# old_motor_line.net
KiCad netlist of a schematic drawn in EAGLE
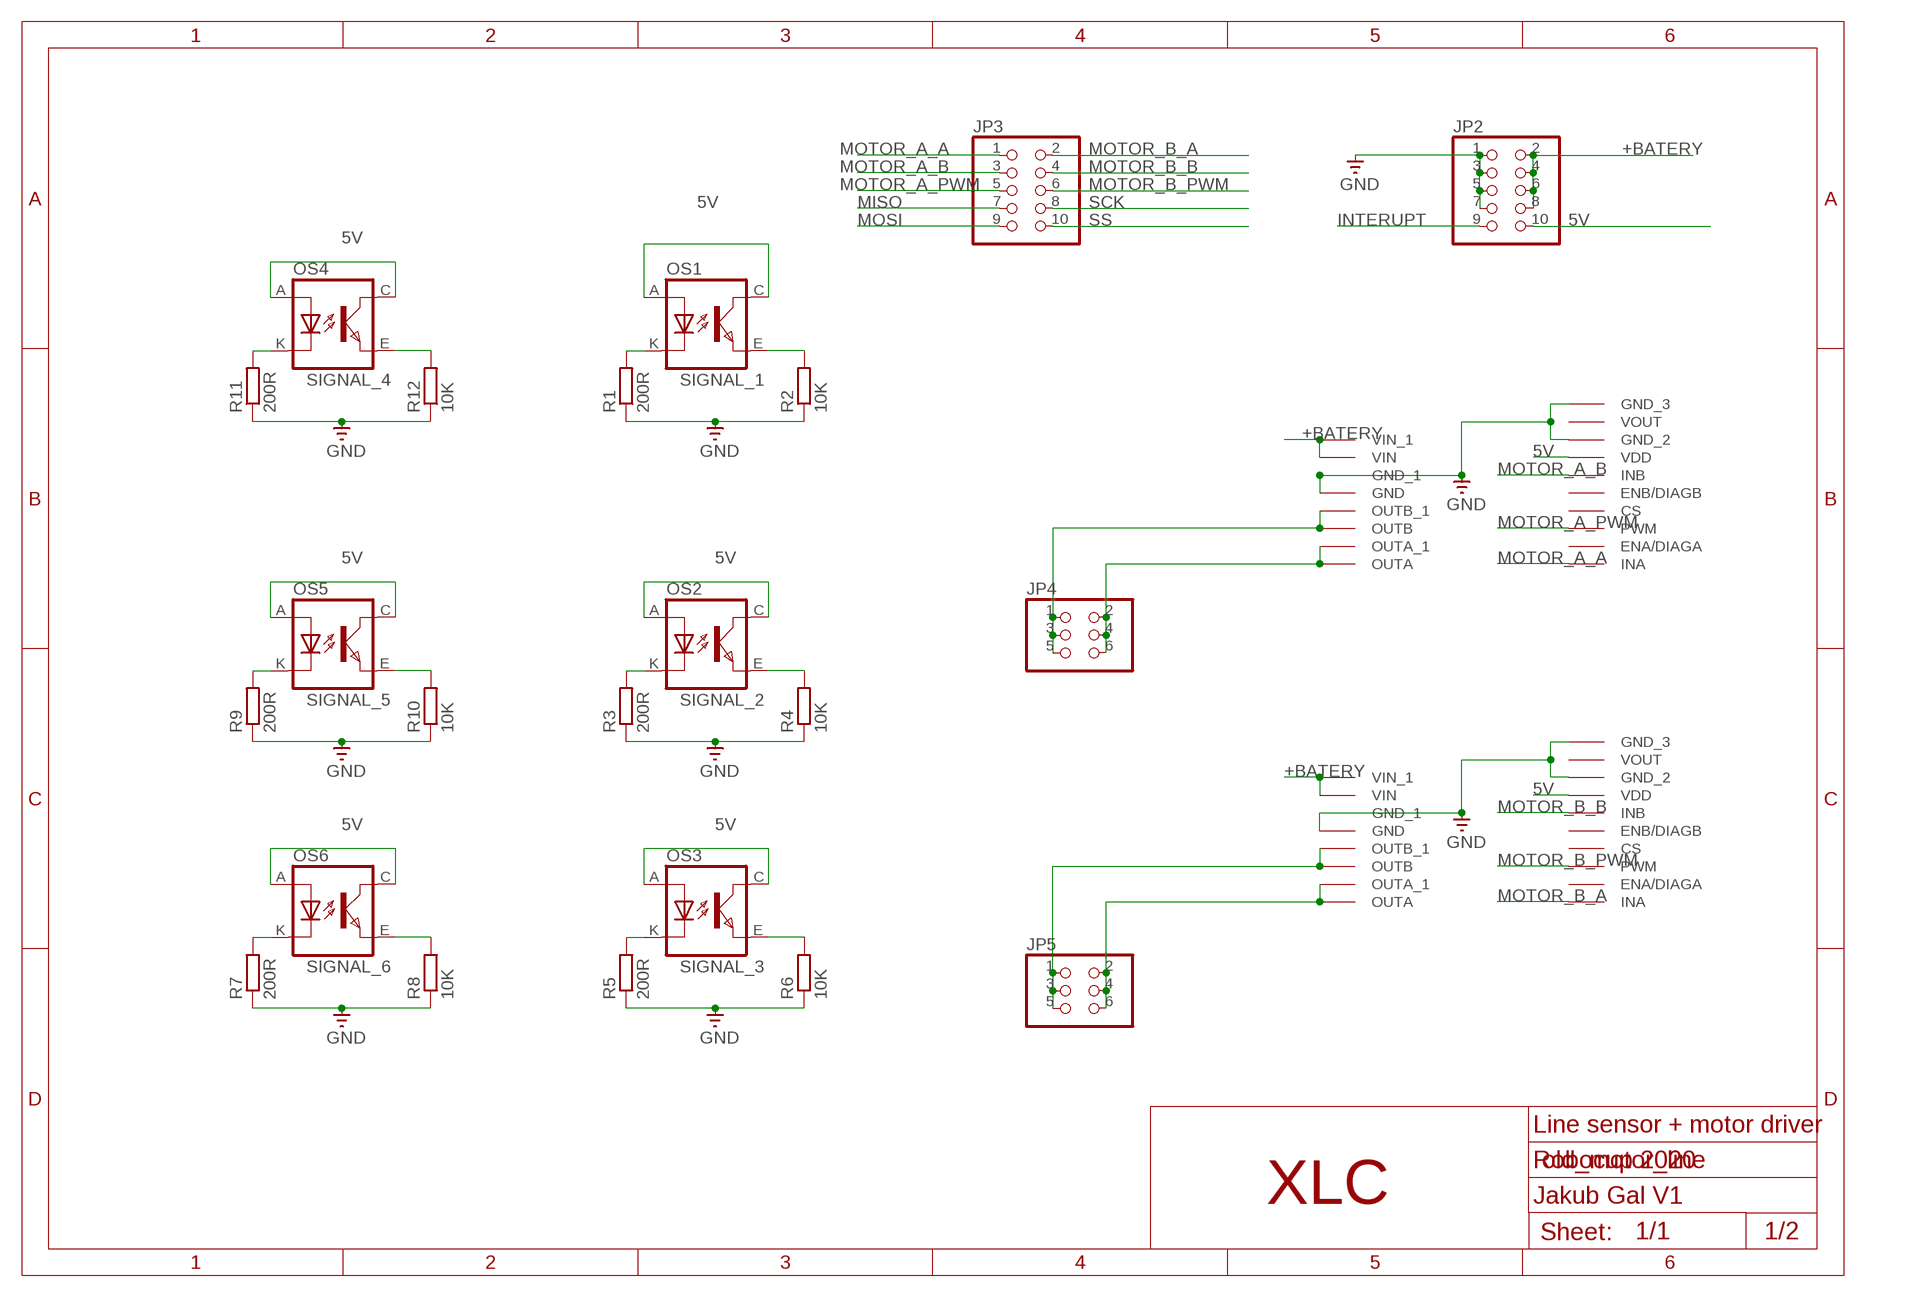
[diagram p0: schematic, sheet 1, part 1 of 2]
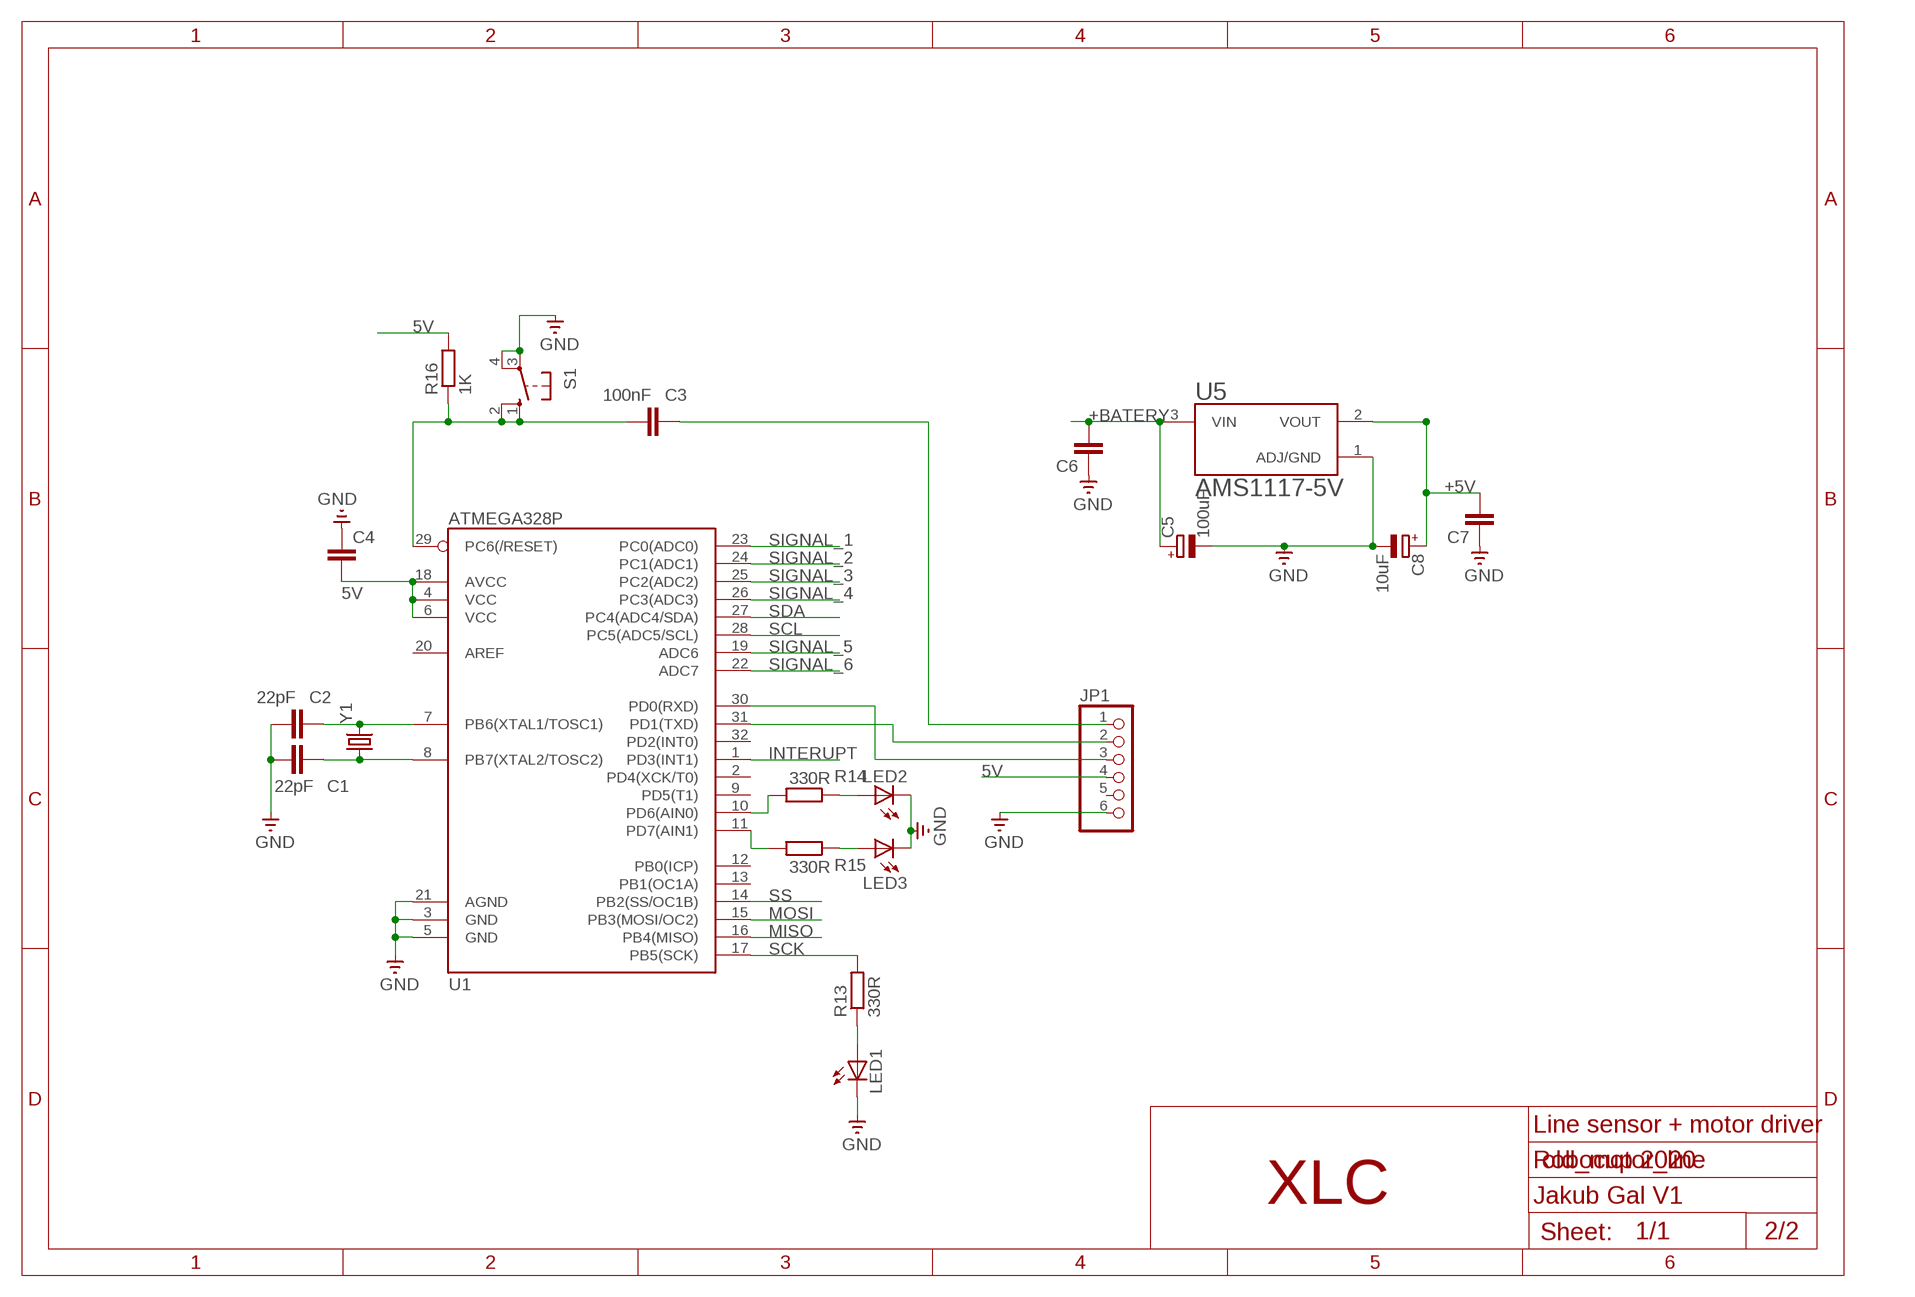
[diagram p1: schematic, sheet 1, part 2 of 2]

(export (version "E")
  (design (tool "Eeschema 10.0.6"))
  (components
    (comp (ref "C1")
      (value "22pF")
      (footprint "eagle-import:C0603")
      (libsource (lib "eagle-import") (part "rcl@1_C-EUC0603"))
    )
    (comp (ref "C2")
      (value "22pF")
      (footprint "eagle-import:C0603")
      (libsource (lib "eagle-import") (part "rcl@1_C-EUC0603"))
    )
    (comp (ref "C3")
      (value "100nF")
      (footprint "eagle-import:C0603")
      (libsource (lib "eagle-import") (part "rcl@1_C-EUC0603"))
    )
    (comp (ref "C4")
      (value "C-EUC0603")
      (footprint "eagle-import:C0603")
      (libsource (lib "eagle-import") (part "C-EUC0603"))
    )
    (comp (ref "C5")
      (value "100uF")
      (footprint "eagle-import:UD-6,3X7,7_NICHICON")
      (libsource (lib "eagle-import") (part "CPOL-EUUD-6,3X7,7"))
    )
    (comp (ref "C6")
      (value "C-EUC0603")
      (footprint "eagle-import:C0603")
      (libsource (lib "eagle-import") (part "C-EUC0603"))
    )
    (comp (ref "C7")
      (value "C-EUC0603")
      (footprint "eagle-import:C0603")
      (libsource (lib "eagle-import") (part "C-EUC0603"))
    )
    (comp (ref "C8")
      (value "10uF")
      (footprint "eagle-import:UD-4X5,8_NICHICON")
      (libsource (lib "eagle-import") (part "CPOL-EUUD-4X5,8"))
    )
    (comp (ref "JP1")
      (value "PINHD-1X6/90")
      (footprint "eagle-import:1X06_90")
      (libsource (lib "eagle-import") (part "PINHD-1X6/90"))
    )
    (comp (ref "JP2")
      (value "PINHD-2X5")
      (footprint "eagle-import:2X05")
      (libsource (lib "eagle-import") (part "PINHD-2X5"))
    )
    (comp (ref "JP3")
      (value "PINHD-2X5")
      (footprint "eagle-import:2X05")
      (libsource (lib "eagle-import") (part "PINHD-2X5"))
    )
    (comp (ref "JP4")
      (value "PINHD-2X3")
      (footprint "eagle-import:2X03")
      (libsource (lib "eagle-import") (part "PINHD-2X3"))
    )
    (comp (ref "JP5")
      (value "PINHD-2X3")
      (footprint "eagle-import:2X03")
      (libsource (lib "eagle-import") (part "PINHD-2X3"))
    )
    (comp (ref "LED1")
      (value "LEDCHIPLED_0603")
      (footprint "eagle-import:CHIPLED_0603")
      (libsource (lib "eagle-import") (part "LEDCHIPLED_0603"))
    )
    (comp (ref "LED2")
      (value "LEDCHIPLED_0603")
      (footprint "eagle-import:CHIPLED_0603")
      (libsource (lib "eagle-import") (part "LEDCHIPLED_0603"))
    )
    (comp (ref "LED3")
      (value "LEDCHIPLED_0603")
      (footprint "eagle-import:CHIPLED_0603")
      (libsource (lib "eagle-import") (part "LEDCHIPLED_0603"))
    )
    (comp (ref "OS1")
      (value "TCRT5000")
      (footprint "eagle-import:TCRT5000")
      (libsource (lib "eagle-import") (part "TCRT5000"))
    )
    (comp (ref "OS2")
      (value "TCRT5000")
      (footprint "eagle-import:TCRT5000")
      (libsource (lib "eagle-import") (part "TCRT5000"))
    )
    (comp (ref "OS3")
      (value "TCRT5000")
      (footprint "eagle-import:TCRT5000")
      (libsource (lib "eagle-import") (part "TCRT5000"))
    )
    (comp (ref "OS4")
      (value "TCRT5000")
      (footprint "eagle-import:TCRT5000")
      (fields (field (name "SPICEPREFIX") "O"))
      (libsource (lib "eagle-import") (part "TCRT5000"))
    )
    (comp (ref "OS5")
      (value "TCRT5000")
      (footprint "eagle-import:TCRT5000")
      (libsource (lib "eagle-import") (part "TCRT5000"))
    )
    (comp (ref "OS6")
      (value "TCRT5000")
      (footprint "eagle-import:TCRT5000")
      (fields (field (name "SPICEPREFIX") "O"))
      (libsource (lib "eagle-import") (part "TCRT5000"))
    )
    (comp (ref "R1")
      (value "200R")
      (footprint "eagle-import:R0603")
      (libsource (lib "eagle-import") (part "R-EU_R0603"))
    )
    (comp (ref "R2")
      (value "10K")
      (footprint "eagle-import:R0603")
      (libsource (lib "eagle-import") (part "R-EU_R0603"))
    )
    (comp (ref "R3")
      (value "200R")
      (footprint "eagle-import:R0603")
      (libsource (lib "eagle-import") (part "R-EU_R0603"))
    )
    (comp (ref "R4")
      (value "10K")
      (footprint "eagle-import:R0603")
      (libsource (lib "eagle-import") (part "R-EU_R0603"))
    )
    (comp (ref "R5")
      (value "200R")
      (footprint "eagle-import:R0603")
      (libsource (lib "eagle-import") (part "R-EU_R0603"))
    )
    (comp (ref "R6")
      (value "10K")
      (footprint "eagle-import:R0603")
      (libsource (lib "eagle-import") (part "R-EU_R0603"))
    )
    (comp (ref "R7")
      (value "200R")
      (footprint "eagle-import:R0603")
      (libsource (lib "eagle-import") (part "R-EU_R0603"))
    )
    (comp (ref "R8")
      (value "10K")
      (footprint "eagle-import:R0603")
      (libsource (lib "eagle-import") (part "R-EU_R0603"))
    )
    (comp (ref "R9")
      (value "200R")
      (footprint "eagle-import:R0603")
      (libsource (lib "eagle-import") (part "R-EU_R0603"))
    )
    (comp (ref "R10")
      (value "10K")
      (footprint "eagle-import:R0603")
      (libsource (lib "eagle-import") (part "R-EU_R0603"))
    )
    (comp (ref "R11")
      (value "200R")
      (footprint "eagle-import:R0603")
      (libsource (lib "eagle-import") (part "R-EU_R0603"))
    )
    (comp (ref "R12")
      (value "10K")
      (footprint "eagle-import:R0603")
      (libsource (lib "eagle-import") (part "R-EU_R0603"))
    )
    (comp (ref "R13")
      (value "330R")
      (footprint "eagle-import:R0603")
      (libsource (lib "eagle-import") (part "R-EU_R0603"))
    )
    (comp (ref "R14")
      (value "330R")
      (footprint "eagle-import:R0603")
      (libsource (lib "eagle-import") (part "R-EU_R0603"))
    )
    (comp (ref "R15")
      (value "330R")
      (footprint "eagle-import:R0603")
      (libsource (lib "eagle-import") (part "R-EU_R0603"))
    )
    (comp (ref "R16")
      (value "1K")
      (footprint "eagle-import:R0603")
      (libsource (lib "eagle-import") (part "R-EU_R0603"))
    )
    (comp (ref "S1")
      (value "10-XX")
      (footprint "eagle-import:B3F-10XX")
      (fields (field (name "MPN") "B3F-1000"))
      (libsource (lib "eagle-import") (part "10-XX"))
    )
    (comp (ref "U$1")
      (value "MOTOR_DRIVER")
      (footprint "eagle-import:MOTOR_DRIVER")
      (libsource (lib "eagle-import") (part "MOTOR_DRIVER"))
    )
    (comp (ref "U$2")
      (value "MOTOR_DRIVER")
      (footprint "eagle-import:MOTOR_DRIVER")
      (libsource (lib "eagle-import") (part "MOTOR_DRIVER"))
    )
    (comp (ref "U1")
      (value "ATMEGA328P")
      (footprint "eagle-import:TQFP32-08")
      (libsource (lib "eagle-import") (part "ATMEGA328_SMT"))
    )
    (comp (ref "U5")
      (value "AMS1117-5V")
      (footprint "eagle-import:SOT229P700X180-4N")
      (fields (field (name "MF") "Advanced Monolithic Systems") (field (name "MP") "AMS1117-3.3"))
      (libsource (lib "eagle-import") (part "AMS1117-3.3"))
    )
    (comp (ref "Y1")
      (value "CRYSTALHC49US")
      (footprint "eagle-import:HC49US")
      (libsource (lib "eagle-import") (part "CRYSTALHC49US"))
    )
  )
  (nets
    (net (code "1") (name "/+5V") (class "Default")
      (node (ref "C7") (pin "2") (pinfunction "2_2") (pintype "passive"))
      (node (ref "C8") (pin "+") (pinfunction "+_+") (pintype "passive"))
      (node (ref "U5") (pin "2") (pinfunction "VOUT_2") (pintype "output"))
    )
    (net (code "2") (name "/+BATERY") (class "Default")
      (node (ref "C5") (pin "+") (pinfunction "+_+") (pintype "passive"))
      (node (ref "C6") (pin "2") (pinfunction "2_2") (pintype "passive"))
      (node (ref "JP2") (pin "2") (pinfunction "2_2") (pintype "passive"))
      (node (ref "JP2") (pin "4") (pinfunction "4_4") (pintype "passive"))
      (node (ref "JP2") (pin "6") (pinfunction "6_6") (pintype "passive"))
      (node (ref "JP2") (pin "8") (pinfunction "8_8") (pintype "passive"))
      (node (ref "U$1") (pin "VIN") (pinfunction "VIN_VIN") (pintype "bidirectional"))
      (node (ref "U$1") (pin "VIN_1") (pinfunction "VIN_1_VIN_1") (pintype "bidirectional"))
      (node (ref "U$2") (pin "VIN") (pinfunction "VIN_VIN") (pintype "bidirectional"))
      (node (ref "U$2") (pin "VIN_1") (pinfunction "VIN_1_VIN_1") (pintype "bidirectional"))
      (node (ref "U5") (pin "3") (pinfunction "VIN_3") (pintype "input"))
    )
    (net (code "3") (name "/5V") (class "Default")
      (node (ref "C4") (pin "2") (pinfunction "2_2") (pintype "passive"))
      (node (ref "JP1") (pin "4") (pinfunction "4_4") (pintype "passive"))
      (node (ref "JP2") (pin "10") (pinfunction "10_10") (pintype "passive"))
      (node (ref "OS1") (pin "A") (pinfunction "ANODE_A") (pintype "passive"))
      (node (ref "OS1") (pin "C") (pinfunction "COLLECTOR_C") (pintype "passive"))
      (node (ref "OS2") (pin "A") (pinfunction "ANODE_A") (pintype "passive"))
      (node (ref "OS2") (pin "C") (pinfunction "COLLECTOR_C") (pintype "passive"))
      (node (ref "OS3") (pin "A") (pinfunction "ANODE_A") (pintype "passive"))
      (node (ref "OS3") (pin "C") (pinfunction "COLLECTOR_C") (pintype "passive"))
      (node (ref "OS4") (pin "A") (pinfunction "ANODE_A") (pintype "passive"))
      (node (ref "OS4") (pin "C") (pinfunction "COLLECTOR_C") (pintype "passive"))
      (node (ref "OS5") (pin "A") (pinfunction "ANODE_A") (pintype "passive"))
      (node (ref "OS5") (pin "C") (pinfunction "COLLECTOR_C") (pintype "passive"))
      (node (ref "OS6") (pin "A") (pinfunction "ANODE_A") (pintype "passive"))
      (node (ref "OS6") (pin "C") (pinfunction "COLLECTOR_C") (pintype "passive"))
      (node (ref "R16") (pin "2") (pinfunction "2_2") (pintype "passive"))
      (node (ref "U$1") (pin "VDD") (pinfunction "VDD_VDD") (pintype "bidirectional"))
      (node (ref "U$2") (pin "VDD") (pinfunction "VDD_VDD") (pintype "bidirectional"))
      (node (ref "U1") (pin "18") (pinfunction "AVCC_18") (pintype "bidirectional"))
      (node (ref "U1") (pin "4") (pinfunction "VCC_4") (pintype "bidirectional"))
      (node (ref "U1") (pin "6") (pinfunction "VCC_6") (pintype "bidirectional"))
    )
    (net (code "4") (name "/INTERUPT") (class "Default")
      (node (ref "JP2") (pin "9") (pinfunction "9_9") (pintype "passive"))
      (node (ref "U1") (pin "1") (pinfunction "PD3(INT1)_1") (pintype "bidirectional"))
    )
    (net (code "5") (name "/MISO") (class "Default")
      (node (ref "JP3") (pin "7") (pinfunction "7_7") (pintype "passive"))
      (node (ref "U1") (pin "16") (pinfunction "PB4(MISO)_16") (pintype "bidirectional"))
    )
    (net (code "6") (name "/MOSI") (class "Default")
      (node (ref "JP3") (pin "9") (pinfunction "9_9") (pintype "passive"))
      (node (ref "U1") (pin "15") (pinfunction "PB3(MOSI/OC2)_15") (pintype "bidirectional"))
    )
    (net (code "7") (name "/MOTOR_A_A") (class "Default")
      (node (ref "JP3") (pin "1") (pinfunction "1_1") (pintype "passive"))
      (node (ref "U$1") (pin "INA") (pinfunction "INA_INA") (pintype "bidirectional"))
    )
    (net (code "8") (name "/MOTOR_A_B") (class "Default")
      (node (ref "JP3") (pin "3") (pinfunction "3_3") (pintype "passive"))
      (node (ref "U$1") (pin "INB") (pinfunction "INB_INB") (pintype "bidirectional"))
    )
    (net (code "9") (name "/MOTOR_A_PWM") (class "Default")
      (node (ref "JP3") (pin "5") (pinfunction "5_5") (pintype "passive"))
      (node (ref "U$1") (pin "PWM") (pinfunction "PWM_PWM") (pintype "bidirectional"))
    )
    (net (code "10") (name "/MOTOR_B_A") (class "Default")
      (node (ref "JP3") (pin "2") (pinfunction "2_2") (pintype "passive"))
      (node (ref "U$2") (pin "INA") (pinfunction "INA_INA") (pintype "bidirectional"))
    )
    (net (code "11") (name "/MOTOR_B_B") (class "Default")
      (node (ref "JP3") (pin "4") (pinfunction "4_4") (pintype "passive"))
      (node (ref "U$2") (pin "INB") (pinfunction "INB_INB") (pintype "bidirectional"))
    )
    (net (code "12") (name "/MOTOR_B_PWM") (class "Default")
      (node (ref "JP3") (pin "6") (pinfunction "6_6") (pintype "passive"))
      (node (ref "U$2") (pin "PWM") (pinfunction "PWM_PWM") (pintype "bidirectional"))
    )
    (net (code "13") (name "/SCK") (class "Default")
      (node (ref "JP3") (pin "8") (pinfunction "8_8") (pintype "passive"))
      (node (ref "R13") (pin "2") (pinfunction "2_2") (pintype "passive"))
      (node (ref "U1") (pin "17") (pinfunction "PB5(SCK)_17") (pintype "bidirectional"))
    )
    (net (code "14") (name "/SCL") (class "Default")
      (node (ref "U1") (pin "28") (pinfunction "PC5(ADC5/SCL)_28") (pintype "bidirectional"))
    )
    (net (code "15") (name "/SDA") (class "Default")
      (node (ref "U1") (pin "27") (pinfunction "PC4(ADC4/SDA)_27") (pintype "bidirectional"))
    )
    (net (code "16") (name "/SIGNAL_1") (class "Default")
      (node (ref "OS1") (pin "E") (pinfunction "EMITTER_E") (pintype "passive"))
      (node (ref "R2") (pin "2") (pinfunction "2_2") (pintype "passive"))
      (node (ref "U1") (pin "23") (pinfunction "PC0(ADC0)_23") (pintype "bidirectional"))
    )
    (net (code "17") (name "/SIGNAL_2") (class "Default")
      (node (ref "OS2") (pin "E") (pinfunction "EMITTER_E") (pintype "passive"))
      (node (ref "R4") (pin "2") (pinfunction "2_2") (pintype "passive"))
      (node (ref "U1") (pin "24") (pinfunction "PC1(ADC1)_24") (pintype "bidirectional"))
    )
    (net (code "18") (name "/SIGNAL_3") (class "Default")
      (node (ref "OS3") (pin "E") (pinfunction "EMITTER_E") (pintype "passive"))
      (node (ref "R6") (pin "2") (pinfunction "2_2") (pintype "passive"))
      (node (ref "U1") (pin "25") (pinfunction "PC2(ADC2)_25") (pintype "bidirectional"))
    )
    (net (code "19") (name "/SIGNAL_4") (class "Default")
      (node (ref "OS4") (pin "E") (pinfunction "EMITTER_E") (pintype "passive"))
      (node (ref "R12") (pin "2") (pinfunction "2_2") (pintype "passive"))
      (node (ref "U1") (pin "26") (pinfunction "PC3(ADC3)_26") (pintype "bidirectional"))
    )
    (net (code "20") (name "/SIGNAL_5") (class "Default")
      (node (ref "OS5") (pin "E") (pinfunction "EMITTER_E") (pintype "passive"))
      (node (ref "R10") (pin "2") (pinfunction "2_2") (pintype "passive"))
      (node (ref "U1") (pin "19") (pinfunction "ADC6_19") (pintype "bidirectional"))
    )
    (net (code "21") (name "/SIGNAL_6") (class "Default")
      (node (ref "OS6") (pin "E") (pinfunction "EMITTER_E") (pintype "passive"))
      (node (ref "R8") (pin "2") (pinfunction "2_2") (pintype "passive"))
      (node (ref "U1") (pin "22") (pinfunction "ADC7_22") (pintype "bidirectional"))
    )
    (net (code "22") (name "/SS") (class "Default")
      (node (ref "JP3") (pin "10") (pinfunction "10_10") (pintype "passive"))
      (node (ref "U1") (pin "14") (pinfunction "PB2(SS/OC1B)_14") (pintype "bidirectional"))
    )
    (net (code "23") (name "GND") (class "Default")
      (node (ref "C1") (pin "1") (pinfunction "1_1") (pintype "passive"))
      (node (ref "C2") (pin "1") (pinfunction "1_1") (pintype "passive"))
      (node (ref "C4") (pin "1") (pinfunction "1_1") (pintype "passive"))
      (node (ref "C5") (pin "-") (pinfunction "-_-") (pintype "passive"))
      (node (ref "C6") (pin "1") (pinfunction "1_1") (pintype "passive"))
      (node (ref "C7") (pin "1") (pinfunction "1_1") (pintype "passive"))
      (node (ref "C8") (pin "-") (pinfunction "-_-") (pintype "passive"))
      (node (ref "JP1") (pin "6") (pinfunction "6_6") (pintype "passive"))
      (node (ref "JP2") (pin "1") (pinfunction "1_1") (pintype "passive"))
      (node (ref "JP2") (pin "3") (pinfunction "3_3") (pintype "passive"))
      (node (ref "JP2") (pin "5") (pinfunction "5_5") (pintype "passive"))
      (node (ref "JP2") (pin "7") (pinfunction "7_7") (pintype "passive"))
      (node (ref "LED1") (pin "C") (pinfunction "C_C") (pintype "passive"))
      (node (ref "LED2") (pin "C") (pinfunction "C_C") (pintype "passive"))
      (node (ref "LED3") (pin "C") (pinfunction "C_C") (pintype "passive"))
      (node (ref "R1") (pin "1") (pinfunction "1_1") (pintype "passive"))
      (node (ref "R10") (pin "1") (pinfunction "1_1") (pintype "passive"))
      (node (ref "R11") (pin "1") (pinfunction "1_1") (pintype "passive"))
      (node (ref "R12") (pin "1") (pinfunction "1_1") (pintype "passive"))
      (node (ref "R2") (pin "1") (pinfunction "1_1") (pintype "passive"))
      (node (ref "R3") (pin "1") (pinfunction "1_1") (pintype "passive"))
      (node (ref "R4") (pin "1") (pinfunction "1_1") (pintype "passive"))
      (node (ref "R5") (pin "1") (pinfunction "1_1") (pintype "passive"))
      (node (ref "R6") (pin "1") (pinfunction "1_1") (pintype "passive"))
      (node (ref "R7") (pin "1") (pinfunction "1_1") (pintype "passive"))
      (node (ref "R8") (pin "1") (pinfunction "1_1") (pintype "passive"))
      (node (ref "R9") (pin "1") (pinfunction "1_1") (pintype "passive"))
      (node (ref "S1") (pin "3") (pinfunction "P_3") (pintype "passive"))
      (node (ref "S1") (pin "4") (pinfunction "P1_4") (pintype "passive"))
      (node (ref "U$1") (pin "GND") (pinfunction "GND_GND") (pintype "bidirectional"))
      (node (ref "U$1") (pin "GND_1") (pinfunction "GND_1_GND_1") (pintype "bidirectional"))
      (node (ref "U$1") (pin "GND_2") (pinfunction "GND_2_GND_2") (pintype "bidirectional"))
      (node (ref "U$1") (pin "GND_3") (pinfunction "GND_3_GND_3") (pintype "bidirectional"))
      (node (ref "U$2") (pin "GND") (pinfunction "GND_GND") (pintype "bidirectional"))
      (node (ref "U$2") (pin "GND_1") (pinfunction "GND_1_GND_1") (pintype "bidirectional"))
      (node (ref "U$2") (pin "GND_2") (pinfunction "GND_2_GND_2") (pintype "bidirectional"))
      (node (ref "U$2") (pin "GND_3") (pinfunction "GND_3_GND_3") (pintype "bidirectional"))
      (node (ref "U1") (pin "21") (pinfunction "AGND_21") (pintype "bidirectional"))
      (node (ref "U1") (pin "3") (pinfunction "GND_3") (pintype "bidirectional"))
      (node (ref "U1") (pin "5") (pinfunction "GND_5") (pintype "bidirectional"))
      (node (ref "U5") (pin "1") (pinfunction "ADJ/GND_1") (pintype "power_in"))
    )
    (net (code "24") (name "Net-(C3-Pad2)") (class "Default")
      (node (ref "C3") (pin "2") (pinfunction "2_2") (pintype "passive"))
      (node (ref "JP1") (pin "1") (pinfunction "1_1") (pintype "passive"))
    )
    (net (code "25") (name "Net-(JP4-Pad1)") (class "Default")
      (node (ref "JP4") (pin "1") (pinfunction "1_1") (pintype "passive"))
      (node (ref "JP4") (pin "3") (pinfunction "3_3") (pintype "passive"))
      (node (ref "JP4") (pin "5") (pinfunction "5_5") (pintype "passive"))
      (node (ref "U$1") (pin "OUTB") (pinfunction "OUTB_OUTB") (pintype "bidirectional"))
      (node (ref "U$1") (pin "OUTB_1") (pinfunction "OUTB_1_OUTB_1") (pintype "bidirectional"))
    )
    (net (code "26") (name "Net-(JP4-Pad2)") (class "Default")
      (node (ref "JP4") (pin "2") (pinfunction "2_2") (pintype "passive"))
      (node (ref "JP4") (pin "4") (pinfunction "4_4") (pintype "passive"))
      (node (ref "JP4") (pin "6") (pinfunction "6_6") (pintype "passive"))
      (node (ref "U$1") (pin "OUTA") (pinfunction "OUTA_OUTA") (pintype "bidirectional"))
      (node (ref "U$1") (pin "OUTA_1") (pinfunction "OUTA_1_OUTA_1") (pintype "bidirectional"))
    )
    (net (code "27") (name "Net-(JP5-Pad1)") (class "Default")
      (node (ref "JP5") (pin "1") (pinfunction "1_1") (pintype "passive"))
      (node (ref "JP5") (pin "3") (pinfunction "3_3") (pintype "passive"))
      (node (ref "JP5") (pin "5") (pinfunction "5_5") (pintype "passive"))
      (node (ref "U$2") (pin "OUTB") (pinfunction "OUTB_OUTB") (pintype "bidirectional"))
      (node (ref "U$2") (pin "OUTB_1") (pinfunction "OUTB_1_OUTB_1") (pintype "bidirectional"))
    )
    (net (code "28") (name "Net-(JP5-Pad2)") (class "Default")
      (node (ref "JP5") (pin "2") (pinfunction "2_2") (pintype "passive"))
      (node (ref "JP5") (pin "4") (pinfunction "4_4") (pintype "passive"))
      (node (ref "JP5") (pin "6") (pinfunction "6_6") (pintype "passive"))
      (node (ref "U$2") (pin "OUTA") (pinfunction "OUTA_OUTA") (pintype "bidirectional"))
      (node (ref "U$2") (pin "OUTA_1") (pinfunction "OUTA_1_OUTA_1") (pintype "bidirectional"))
    )
    (net (code "29") (name "Net-(LED1-PadA)") (class "Default")
      (node (ref "LED1") (pin "A") (pinfunction "A_A") (pintype "passive"))
      (node (ref "R13") (pin "1") (pinfunction "1_1") (pintype "passive"))
    )
    (net (code "30") (name "Net-(LED2-PadA)") (class "Default")
      (node (ref "LED2") (pin "A") (pinfunction "A_A") (pintype "passive"))
      (node (ref "R14") (pin "1") (pinfunction "1_1") (pintype "passive"))
    )
    (net (code "31") (name "Net-(LED3-PadA)") (class "Default")
      (node (ref "LED3") (pin "A") (pinfunction "A_A") (pintype "passive"))
      (node (ref "R15") (pin "1") (pinfunction "1_1") (pintype "passive"))
    )
    (net (code "32") (name "Net-(OS1-CATHODE)") (class "Default")
      (node (ref "OS1") (pin "K") (pinfunction "CATHODE_K") (pintype "passive"))
      (node (ref "R1") (pin "2") (pinfunction "2_2") (pintype "passive"))
    )
    (net (code "33") (name "Net-(OS2-CATHODE)") (class "Default")
      (node (ref "OS2") (pin "K") (pinfunction "CATHODE_K") (pintype "passive"))
      (node (ref "R3") (pin "2") (pinfunction "2_2") (pintype "passive"))
    )
    (net (code "34") (name "Net-(OS3-CATHODE)") (class "Default")
      (node (ref "OS3") (pin "K") (pinfunction "CATHODE_K") (pintype "passive"))
      (node (ref "R5") (pin "2") (pinfunction "2_2") (pintype "passive"))
    )
    (net (code "35") (name "Net-(OS4-CATHODE)") (class "Default")
      (node (ref "OS4") (pin "K") (pinfunction "CATHODE_K") (pintype "passive"))
      (node (ref "R11") (pin "2") (pinfunction "2_2") (pintype "passive"))
    )
    (net (code "36") (name "Net-(OS5-CATHODE)") (class "Default")
      (node (ref "OS5") (pin "K") (pinfunction "CATHODE_K") (pintype "passive"))
      (node (ref "R9") (pin "2") (pinfunction "2_2") (pintype "passive"))
    )
    (net (code "37") (name "Net-(OS6-CATHODE)") (class "Default")
      (node (ref "OS6") (pin "K") (pinfunction "CATHODE_K") (pintype "passive"))
      (node (ref "R7") (pin "2") (pinfunction "2_2") (pintype "passive"))
    )
    (net (code "38") (name "Net-(S1-S)") (class "Default")
      (node (ref "C3") (pin "1") (pinfunction "1_1") (pintype "passive"))
      (node (ref "R16") (pin "1") (pinfunction "1_1") (pintype "passive"))
      (node (ref "S1") (pin "1") (pinfunction "S_1") (pintype "passive"))
      (node (ref "S1") (pin "2") (pinfunction "S1_2") (pintype "passive"))
      (node (ref "U1") (pin "29") (pinfunction "PC6(/RESET)_29") (pintype "bidirectional"))
    )
    (net (code "39") (name "Net-(U1-PB6(XTAL1{slash}TOSC1))") (class "Default")
      (node (ref "C2") (pin "2") (pinfunction "2_2") (pintype "passive"))
      (node (ref "U1") (pin "7") (pinfunction "PB6(XTAL1/TOSC1)_7") (pintype "bidirectional"))
      (node (ref "Y1") (pin "2") (pinfunction "2_2") (pintype "passive"))
    )
    (net (code "40") (name "Net-(U1-PB7(XTAL2{slash}TOSC2))") (class "Default")
      (node (ref "C1") (pin "2") (pinfunction "2_2") (pintype "passive"))
      (node (ref "U1") (pin "8") (pinfunction "PB7(XTAL2/TOSC2)_8") (pintype "bidirectional"))
      (node (ref "Y1") (pin "1") (pinfunction "1_1") (pintype "passive"))
    )
    (net (code "41") (name "Net-(U1-PD0(RXD))") (class "Default")
      (node (ref "JP1") (pin "3") (pinfunction "3_3") (pintype "passive"))
      (node (ref "U1") (pin "30") (pinfunction "PD0(RXD)_30") (pintype "bidirectional"))
    )
    (net (code "42") (name "Net-(U1-PD1(TXD))") (class "Default")
      (node (ref "JP1") (pin "2") (pinfunction "2_2") (pintype "passive"))
      (node (ref "U1") (pin "31") (pinfunction "PD1(TXD)_31") (pintype "bidirectional"))
    )
    (net (code "43") (name "Net-(U1-PD6(AIN0))") (class "Default")
      (node (ref "R14") (pin "2") (pinfunction "2_2") (pintype "passive"))
      (node (ref "U1") (pin "10") (pinfunction "PD6(AIN0)_10") (pintype "bidirectional"))
    )
    (net (code "44") (name "Net-(U1-PD7(AIN1))") (class "Default")
      (node (ref "R15") (pin "2") (pinfunction "2_2") (pintype "passive"))
      (node (ref "U1") (pin "11") (pinfunction "PD7(AIN1)_11") (pintype "bidirectional"))
    )
    (net (code "45") (name "unconnected-(JP1-Pad5)") (class "Default")
      (node (ref "JP1") (pin "5") (pinfunction "5_5") (pintype "passive"))
    )
    (net (code "46") (name "unconnected-(U$1-PadCS)") (class "Default")
      (node (ref "U$1") (pin "CS") (pinfunction "CS_CS") (pintype "bidirectional"))
    )
    (net (code "47") (name "unconnected-(U$1-PadENA{slash}DIAGA)") (class "Default")
      (node (ref "U$1") (pin "ENA/DIAGA") (pinfunction "ENA/DIAGA_ENA/DIAGA") (pintype "bidirectional"))
    )
    (net (code "48") (name "unconnected-(U$1-PadENB{slash}DIAGB)") (class "Default")
      (node (ref "U$1") (pin "ENB/DIAGB") (pinfunction "ENB/DIAGB_ENB/DIAGB") (pintype "bidirectional"))
    )
    (net (code "49") (name "unconnected-(U$1-PadVOUT)") (class "Default")
      (node (ref "U$1") (pin "VOUT") (pinfunction "VOUT_VOUT") (pintype "bidirectional"))
    )
    (net (code "50") (name "unconnected-(U$2-PadCS)") (class "Default")
      (node (ref "U$2") (pin "CS") (pinfunction "CS_CS") (pintype "bidirectional"))
    )
    (net (code "51") (name "unconnected-(U$2-PadENA{slash}DIAGA)") (class "Default")
      (node (ref "U$2") (pin "ENA/DIAGA") (pinfunction "ENA/DIAGA_ENA/DIAGA") (pintype "bidirectional"))
    )
    (net (code "52") (name "unconnected-(U$2-PadENB{slash}DIAGB)") (class "Default")
      (node (ref "U$2") (pin "ENB/DIAGB") (pinfunction "ENB/DIAGB_ENB/DIAGB") (pintype "bidirectional"))
    )
    (net (code "53") (name "unconnected-(U$2-PadVOUT)") (class "Default")
      (node (ref "U$2") (pin "VOUT") (pinfunction "VOUT_VOUT") (pintype "bidirectional"))
    )
    (net (code "54") (name "unconnected-(U1-AREF-Pad20)") (class "Default")
      (node (ref "U1") (pin "20") (pinfunction "AREF_20") (pintype "bidirectional"))
    )
    (net (code "55") (name "unconnected-(U1-PB0(ICP)-Pad12)") (class "Default")
      (node (ref "U1") (pin "12") (pinfunction "PB0(ICP)_12") (pintype "bidirectional"))
    )
    (net (code "56") (name "unconnected-(U1-PB1(OC1A)-Pad13)") (class "Default")
      (node (ref "U1") (pin "13") (pinfunction "PB1(OC1A)_13") (pintype "bidirectional"))
    )
    (net (code "57") (name "unconnected-(U1-PD2(INT0)-Pad32)") (class "Default")
      (node (ref "U1") (pin "32") (pinfunction "PD2(INT0)_32") (pintype "bidirectional"))
    )
    (net (code "58") (name "unconnected-(U1-PD4(XCK{slash}T0)-Pad2)") (class "Default")
      (node (ref "U1") (pin "2") (pinfunction "PD4(XCK/T0)_2") (pintype "bidirectional"))
    )
    (net (code "59") (name "unconnected-(U1-PD5(T1)-Pad9)") (class "Default")
      (node (ref "U1") (pin "9") (pinfunction "PD5(T1)_9") (pintype "bidirectional"))
    )
  )
)
